# EnvFollower.net
KiCad netlist of a schematic drawn in EAGLE
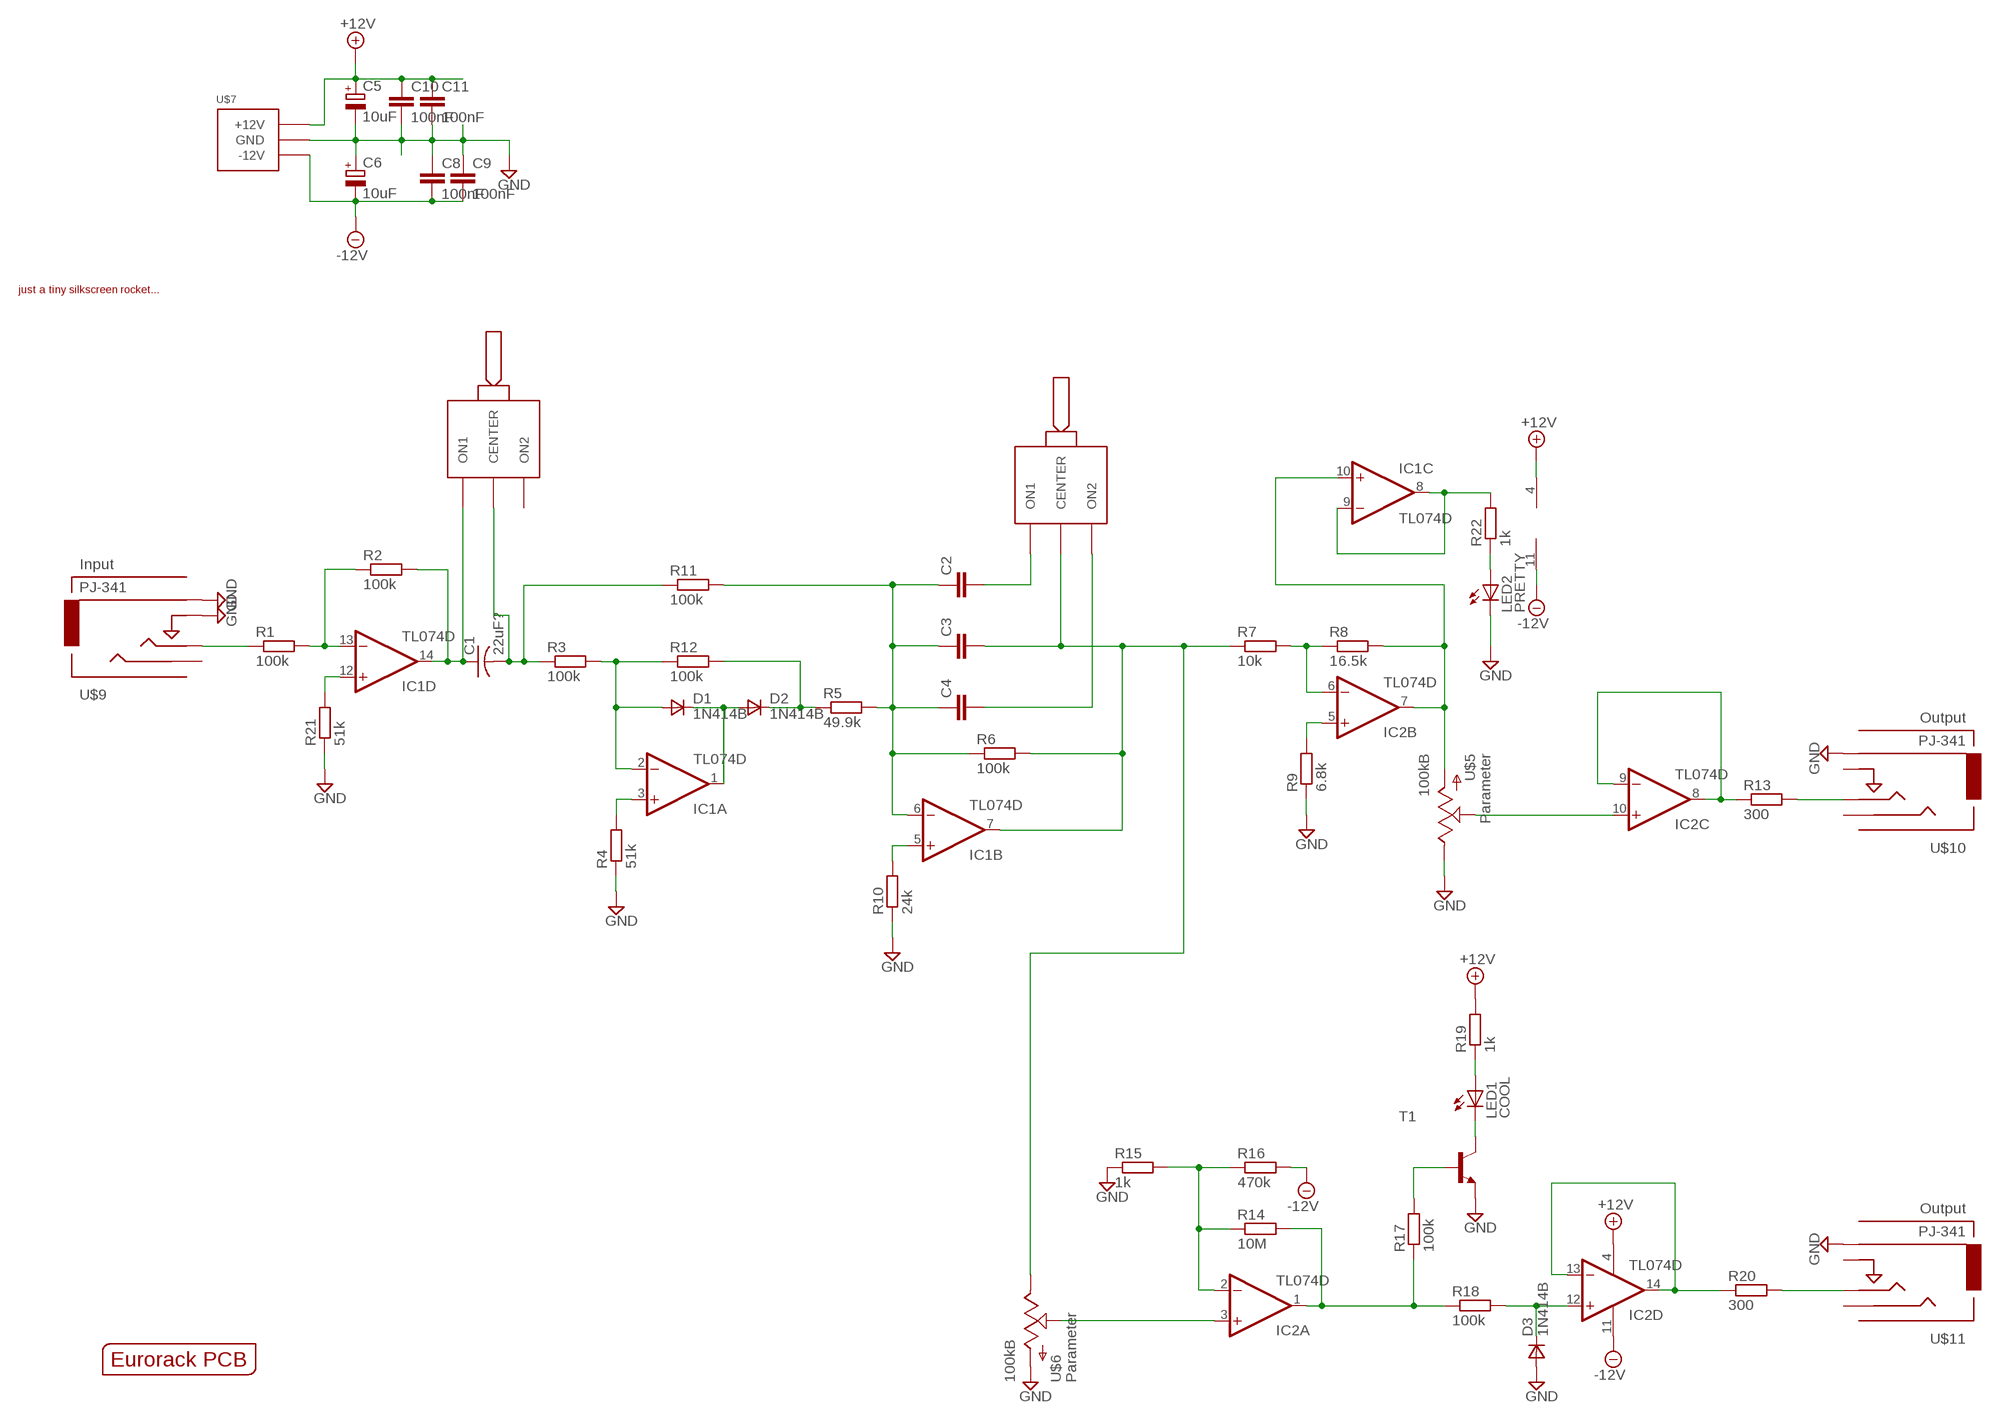
[diagram p0: schematic, sheet 1]

(export (version "E")
  (design (tool "Eeschema 10.0.6"))
  (components
    (comp (ref "C1")
      (value "22uF?")
      (footprint "eagle-import:C1210K")
      (libsource (lib "eagle-import") (part "C-USC1210K"))
    )
    (comp (ref "C2")
      (value "C-EUC0603K")
      (footprint "eagle-import:C0603K")
      (libsource (lib "eagle-import") (part "C-EUC0603K"))
    )
    (comp (ref "C3")
      (value "C-EUC0603K")
      (footprint "eagle-import:C0603K")
      (libsource (lib "eagle-import") (part "C-EUC0603K"))
    )
    (comp (ref "C4")
      (value "C-EUC0603K")
      (footprint "eagle-import:C0603K")
      (libsource (lib "eagle-import") (part "C-EUC0603K"))
    )
    (comp (ref "C5")
      (value "10uF")
      (footprint "eagle-import:153CLV-0505")
      (libsource (lib "eagle-import") (part "CPOL-EU153CLV-0505"))
    )
    (comp (ref "C6")
      (value "10uF")
      (footprint "eagle-import:153CLV-0505")
      (libsource (lib "eagle-import") (part "CPOL-EU153CLV-0505"))
    )
    (comp (ref "C8")
      (value "100nF")
      (footprint "eagle-import:C0603K")
      (libsource (lib "eagle-import") (part "C-EUC0603K"))
    )
    (comp (ref "C9")
      (value "100nF")
      (footprint "eagle-import:C0603K")
      (libsource (lib "eagle-import") (part "C-EUC0603K"))
    )
    (comp (ref "C10")
      (value "100nF")
      (footprint "eagle-import:C0603K")
      (libsource (lib "eagle-import") (part "C-EUC0603K"))
    )
    (comp (ref "C11")
      (value "100nF")
      (footprint "eagle-import:C0603K")
      (libsource (lib "eagle-import") (part "C-EUC0603K"))
    )
    (comp (ref "D1")
      (value "1N414B")
      (footprint "eagle-import:SOT-23")
      (fields (field (name "MPN") "CDSOT23-T03"))
      (libsource (lib "eagle-import") (part "DSOT23"))
    )
    (comp (ref "D2")
      (value "1N414B")
      (footprint "eagle-import:SOT-23")
      (fields (field (name "MPN") "CDSOT23-T03"))
      (libsource (lib "eagle-import") (part "DSOT23"))
    )
    (comp (ref "D3")
      (value "1N414B")
      (footprint "eagle-import:SOT-23")
      (fields (field (name "MPN") "CDSOT23-T03"))
      (libsource (lib "eagle-import") (part "DSOT23"))
    )
    (comp (ref "IC1")
      (value "TL074D")
      (footprint "eagle-import:SO14")
      (libsource (lib "eagle-import") (part "TL074D"))
    )
    (comp (ref "IC2")
      (value "TL074D")
      (footprint "eagle-import:SO14")
      (libsource (lib "eagle-import") (part "TL074D"))
    )
    (comp (ref "LED1")
      (value "COOL")
      (footprint "eagle-import:LED3MM")
      (libsource (lib "eagle-import") (part "LED3MM"))
    )
    (comp (ref "LED2")
      (value "PRETTY")
      (footprint "eagle-import:LED3MM")
      (libsource (lib "eagle-import") (part "LED3MM"))
    )
    (comp (ref "R1")
      (value "100k")
      (footprint "eagle-import:R0603")
      (libsource (lib "eagle-import") (part "R-EU_R0603"))
    )
    (comp (ref "R2")
      (value "100k")
      (footprint "eagle-import:R0603")
      (libsource (lib "eagle-import") (part "R-EU_R0603"))
    )
    (comp (ref "R3")
      (value "100k")
      (footprint "eagle-import:R0603")
      (libsource (lib "eagle-import") (part "R-EU_R0603"))
    )
    (comp (ref "R4")
      (value "51k")
      (footprint "eagle-import:R0603")
      (libsource (lib "eagle-import") (part "R-EU_R0603"))
    )
    (comp (ref "R5")
      (value "49.9k")
      (footprint "eagle-import:R0603")
      (libsource (lib "eagle-import") (part "R-EU_R0603"))
    )
    (comp (ref "R6")
      (value "100k")
      (footprint "eagle-import:R0603")
      (libsource (lib "eagle-import") (part "R-EU_R0603"))
    )
    (comp (ref "R7")
      (value "10k")
      (footprint "eagle-import:R0603")
      (libsource (lib "eagle-import") (part "R-EU_R0603"))
    )
    (comp (ref "R8")
      (value "16.5k")
      (footprint "eagle-import:R0603")
      (libsource (lib "eagle-import") (part "R-EU_R0603"))
    )
    (comp (ref "R9")
      (value "6.8k")
      (footprint "eagle-import:R0603")
      (libsource (lib "eagle-import") (part "R-EU_R0603"))
    )
    (comp (ref "R10")
      (value "24k")
      (footprint "eagle-import:R0603")
      (libsource (lib "eagle-import") (part "R-EU_R0603"))
    )
    (comp (ref "R11")
      (value "100k")
      (footprint "eagle-import:R0603")
      (libsource (lib "eagle-import") (part "R-EU_R0603"))
    )
    (comp (ref "R12")
      (value "100k")
      (footprint "eagle-import:R0603")
      (libsource (lib "eagle-import") (part "R-EU_R0603"))
    )
    (comp (ref "R13")
      (value "300")
      (footprint "eagle-import:R0603")
      (libsource (lib "eagle-import") (part "R-EU_R0603"))
    )
    (comp (ref "R14")
      (value "10M")
      (footprint "eagle-import:R0603")
      (libsource (lib "eagle-import") (part "R-EU_R0603"))
    )
    (comp (ref "R15")
      (value "1k")
      (footprint "eagle-import:R0603")
      (libsource (lib "eagle-import") (part "R-EU_R0603"))
    )
    (comp (ref "R16")
      (value "470k")
      (footprint "eagle-import:R0603")
      (libsource (lib "eagle-import") (part "R-EU_R0603"))
    )
    (comp (ref "R17")
      (value "100k")
      (footprint "eagle-import:R0603")
      (libsource (lib "eagle-import") (part "R-EU_R0603"))
    )
    (comp (ref "R18")
      (value "100k")
      (footprint "eagle-import:R0603")
      (libsource (lib "eagle-import") (part "R-EU_R0603"))
    )
    (comp (ref "R19")
      (value "1k")
      (footprint "eagle-import:R0603")
      (libsource (lib "eagle-import") (part "R-EU_R0603"))
    )
    (comp (ref "R20")
      (value "300")
      (footprint "eagle-import:R0603")
      (libsource (lib "eagle-import") (part "R-EU_R0603"))
    )
    (comp (ref "R21")
      (value "51k")
      (footprint "eagle-import:R0603")
      (libsource (lib "eagle-import") (part "R-EU_R0603"))
    )
    (comp (ref "R22")
      (value "1k")
      (footprint "eagle-import:R0603")
      (libsource (lib "eagle-import") (part "R-EU_R0603"))
    )
    (comp (ref "T1")
      (value "BCX70-NPN-SOT23-BEC")
      (footprint "eagle-import:SOT23-BEC")
      (libsource (lib "eagle-import") (part "-NPN-SOT23-BECBCX70"))
    )
    (comp (ref "U$1")
      (value "EURORACK_PCB4HP")
      (footprint "eagle-import:EURORACK4HPPCB")
      (libsource (lib "eagle-import") (part "EURORACK_PCB4HP"))
    )
    (comp (ref "U$2")
      (value "JUSTATINYROCKET")
      (footprint "eagle-import:JUSTATINYROCKET")
      (libsource (lib "eagle-import") (part "JUSTATINYROCKET"))
    )
    (comp (ref "U$4")
      (value "ONOFFON")
      (footprint "eagle-import:MULTICOMP1MS-ONOFFON")
      (libsource (lib "eagle-import") (part "ONOFFON"))
    )
    (comp (ref "U$5")
      (value "100kB")
      (footprint "eagle-import:OG-POTS_ALPS_POT_VERTICAL")
      (libsource (lib "eagle-import") (part "POTZEPHPOT"))
    )
    (comp (ref "U$6")
      (value "100kB")
      (footprint "eagle-import:OG-POTS_ALPS_POT_VERTICAL")
      (libsource (lib "eagle-import") (part "POTZEPHPOT"))
    )
    (comp (ref "U$7")
      (value "POWER_SIMPLE10-OTHERSIDE")
      (footprint "eagle-import:POWER_10_LABELSOTHERSIDE")
      (libsource (lib "eagle-import") (part "POWER_SIMPLE10-OTHERSIDE"))
    )
    (comp (ref "U$8")
      (value "ONOFFON")
      (footprint "eagle-import:MULTICOMP1MS-ONOFFON")
      (libsource (lib "eagle-import") (part "ONOFFON"))
    )
    (comp (ref "U$9")
      (value "PJ-341")
      (footprint "eagle-import:3.5MM-JACK-SWITCH-13MM-INPUT")
      (libsource (lib "eagle-import") (part "AUDIO-JACKINPUT"))
    )
    (comp (ref "U$10")
      (value "PJ-341")
      (footprint "eagle-import:3.5MM-JACK-SWITCH-13MM-OUTPUT")
      (libsource (lib "eagle-import") (part "AUDIO-JACKOUTPUT"))
    )
    (comp (ref "U$11")
      (value "PJ-341")
      (footprint "eagle-import:3.5MM-JACK-SWITCH-13MM-OUTPUT")
      (libsource (lib "eagle-import") (part "AUDIO-JACKOUTPUT"))
    )
  )
  (nets
    (net (code "1") (name "+12V") (class "Default")
      (node (ref "C10") (pin "1") (pinfunction "1_1") (pintype "passive"))
      (node (ref "C11") (pin "1") (pinfunction "1_1") (pintype "passive"))
      (node (ref "C5") (pin "+") (pinfunction "+_+") (pintype "passive"))
      (node (ref "IC1") (pin "4") (pinfunction "V+_4") (pintype "power_in"))
      (node (ref "IC2") (pin "4") (pinfunction "V+_4") (pintype "power_in"))
      (node (ref "R19") (pin "2") (pinfunction "2_2") (pintype "passive"))
      (node (ref "U$7") (pin "10") (pinfunction "+12V_10") (pintype "bidirectional"))
      (node (ref "U$7") (pin "9") (pinfunction "+12V_9") (pintype "bidirectional"))
    )
    (net (code "2") (name "-12V") (class "Default")
      (node (ref "C6") (pin "-") (pinfunction "-_-") (pintype "passive"))
      (node (ref "C8") (pin "2") (pinfunction "2_2") (pintype "passive"))
      (node (ref "C9") (pin "2") (pinfunction "2_2") (pintype "passive"))
      (node (ref "IC1") (pin "11") (pinfunction "V-_11") (pintype "power_in"))
      (node (ref "IC2") (pin "11") (pinfunction "V-_11") (pintype "power_in"))
      (node (ref "R16") (pin "2") (pinfunction "2_2") (pintype "passive"))
      (node (ref "U$7") (pin "1") (pinfunction "-12V_1") (pintype "bidirectional"))
      (node (ref "U$7") (pin "2") (pinfunction "-12V_2") (pintype "bidirectional"))
    )
    (net (code "3") (name "GND") (class "Default")
      (node (ref "C10") (pin "2") (pinfunction "2_2") (pintype "passive"))
      (node (ref "C11") (pin "2") (pinfunction "2_2") (pintype "passive"))
      (node (ref "C5") (pin "-") (pinfunction "-_-") (pintype "passive"))
      (node (ref "C6") (pin "+") (pinfunction "+_+") (pintype "passive"))
      (node (ref "C8") (pin "1") (pinfunction "1_1") (pintype "passive"))
      (node (ref "C9") (pin "1") (pinfunction "1_1") (pintype "passive"))
      (node (ref "D3") (pin "3") (pinfunction "A_3") (pintype "passive"))
      (node (ref "LED2") (pin "K") (pinfunction "C_K") (pintype "passive"))
      (node (ref "R10") (pin "1") (pinfunction "1_1") (pintype "passive"))
      (node (ref "R15") (pin "1") (pinfunction "1_1") (pintype "passive"))
      (node (ref "R21") (pin "1") (pinfunction "1_1") (pintype "passive"))
      (node (ref "R4") (pin "1") (pinfunction "1_1") (pintype "passive"))
      (node (ref "R9") (pin "1") (pinfunction "1_1") (pintype "passive"))
      (node (ref "T1") (pin "E") (pinfunction "E_E") (pintype "passive"))
      (node (ref "U$10") (pin "RING@3") (pinfunction "RING_RING@3") (pintype "bidirectional"))
      (node (ref "U$11") (pin "RING@3") (pinfunction "RING_RING@3") (pintype "bidirectional"))
      (node (ref "U$5") (pin "P$1") (pinfunction "E_P$1") (pintype "passive"))
      (node (ref "U$6") (pin "P$3") (pinfunction "A_P$3") (pintype "passive"))
      (node (ref "U$7") (pin "3") (pinfunction "GND_3") (pintype "bidirectional"))
      (node (ref "U$7") (pin "4") (pinfunction "GND_4") (pintype "bidirectional"))
      (node (ref "U$7") (pin "5") (pinfunction "GND_5") (pintype "bidirectional"))
      (node (ref "U$7") (pin "6") (pinfunction "GND_6") (pintype "bidirectional"))
      (node (ref "U$7") (pin "7") (pinfunction "GND_7") (pintype "bidirectional"))
      (node (ref "U$7") (pin "8") (pinfunction "GND_8") (pintype "bidirectional"))
      (node (ref "U$9") (pin "RING@3") (pinfunction "RING_RING@3") (pintype "bidirectional"))
      (node (ref "U$9") (pin "SWITCH@3") (pinfunction "SWITCH_SWITCH@3") (pintype "bidirectional"))
    )
    (net (code "4") (name "Net-(D1-A)") (class "Default")
      (node (ref "D1") (pin "3") (pinfunction "A_3") (pintype "passive"))
      (node (ref "IC1") (pin "2") (pinfunction "-IN_2") (pintype "input"))
      (node (ref "R12") (pin "1") (pinfunction "1_1") (pintype "passive"))
      (node (ref "R3") (pin "2") (pinfunction "2_2") (pintype "passive"))
    )
    (net (code "5") (name "Net-(D1-C)") (class "Default")
      (node (ref "D1") (pin "1") (pinfunction "C_1") (pintype "passive"))
      (node (ref "D2") (pin "3") (pinfunction "A_3") (pintype "passive"))
      (node (ref "IC1") (pin "1") (pinfunction "OUT_1") (pintype "output"))
    )
    (net (code "6") (name "Net-(D2-C)") (class "Default")
      (node (ref "D2") (pin "1") (pinfunction "C_1") (pintype "passive"))
      (node (ref "R12") (pin "2") (pinfunction "2_2") (pintype "passive"))
      (node (ref "R5") (pin "1") (pinfunction "1_1") (pintype "passive"))
    )
    (net (code "7") (name "Net-(D3-C)") (class "Default")
      (node (ref "D3") (pin "1") (pinfunction "C_1") (pintype "passive"))
      (node (ref "IC2") (pin "12") (pinfunction "+IN_12") (pintype "input"))
      (node (ref "R18") (pin "2") (pinfunction "2_2") (pintype "passive"))
    )
    (net (code "8") (name "Net-(IC1A-+IN)") (class "Default")
      (node (ref "IC1") (pin "3") (pinfunction "+IN_3") (pintype "input"))
      (node (ref "R4") (pin "2") (pinfunction "2_2") (pintype "passive"))
    )
    (net (code "9") (name "Net-(IC1B-+IN)") (class "Default")
      (node (ref "IC1") (pin "5") (pinfunction "+IN_5") (pintype "input"))
      (node (ref "R10") (pin "2") (pinfunction "2_2") (pintype "passive"))
    )
    (net (code "10") (name "Net-(IC1B--IN)") (class "Default")
      (node (ref "C2") (pin "1") (pinfunction "1_1") (pintype "passive"))
      (node (ref "C3") (pin "1") (pinfunction "1_1") (pintype "passive"))
      (node (ref "C4") (pin "1") (pinfunction "1_1") (pintype "passive"))
      (node (ref "IC1") (pin "6") (pinfunction "-IN_6") (pintype "input"))
      (node (ref "R11") (pin "2") (pinfunction "2_2") (pintype "passive"))
      (node (ref "R5") (pin "2") (pinfunction "2_2") (pintype "passive"))
      (node (ref "R6") (pin "1") (pinfunction "1_1") (pintype "passive"))
    )
    (net (code "11") (name "Net-(IC1B-OUT)") (class "Default")
      (node (ref "C3") (pin "2") (pinfunction "2_2") (pintype "passive"))
      (node (ref "IC1") (pin "7") (pinfunction "OUT_7") (pintype "output"))
      (node (ref "R6") (pin "2") (pinfunction "2_2") (pintype "passive"))
      (node (ref "R7") (pin "1") (pinfunction "1_1") (pintype "passive"))
      (node (ref "U$6") (pin "P$1") (pinfunction "E_P$1") (pintype "passive"))
      (node (ref "U$8") (pin "2") (pinfunction "CENTER_2") (pintype "bidirectional"))
    )
    (net (code "12") (name "Net-(IC1C-+IN)") (class "Default")
      (node (ref "IC1") (pin "10") (pinfunction "+IN_10") (pintype "input"))
      (node (ref "IC2") (pin "7") (pinfunction "OUT_7") (pintype "output"))
      (node (ref "R8") (pin "2") (pinfunction "2_2") (pintype "passive"))
      (node (ref "U$5") (pin "P$3") (pinfunction "A_P$3") (pintype "passive"))
    )
    (net (code "13") (name "Net-(IC1C--IN)") (class "Default")
      (node (ref "IC1") (pin "8") (pinfunction "OUT_8") (pintype "output"))
      (node (ref "IC1") (pin "9") (pinfunction "-IN_9") (pintype "input"))
      (node (ref "R22") (pin "2") (pinfunction "2_2") (pintype "passive"))
    )
    (net (code "14") (name "Net-(IC1D-+IN)") (class "Default")
      (node (ref "IC1") (pin "12") (pinfunction "+IN_12") (pintype "input"))
      (node (ref "R21") (pin "2") (pinfunction "2_2") (pintype "passive"))
    )
    (net (code "15") (name "Net-(IC1D--IN)") (class "Default")
      (node (ref "IC1") (pin "13") (pinfunction "-IN_13") (pintype "input"))
      (node (ref "R1") (pin "2") (pinfunction "2_2") (pintype "passive"))
      (node (ref "R2") (pin "1") (pinfunction "1_1") (pintype "passive"))
    )
    (net (code "16") (name "Net-(IC1D-OUT)") (class "Default")
      (node (ref "C1") (pin "1") (pinfunction "1_1") (pintype "passive"))
      (node (ref "IC1") (pin "14") (pinfunction "OUT_14") (pintype "output"))
      (node (ref "R2") (pin "2") (pinfunction "2_2") (pintype "passive"))
      (node (ref "U$4") (pin "1") (pinfunction "ON1_1") (pintype "bidirectional"))
    )
    (net (code "17") (name "Net-(IC2A-+IN)") (class "Default")
      (node (ref "IC2") (pin "3") (pinfunction "+IN_3") (pintype "input"))
      (node (ref "U$6") (pin "P$2") (pinfunction "S_P$2") (pintype "passive"))
    )
    (net (code "18") (name "Net-(IC2A--IN)") (class "Default")
      (node (ref "IC2") (pin "2") (pinfunction "-IN_2") (pintype "input"))
      (node (ref "R14") (pin "1") (pinfunction "1_1") (pintype "passive"))
      (node (ref "R15") (pin "2") (pinfunction "2_2") (pintype "passive"))
      (node (ref "R16") (pin "1") (pinfunction "1_1") (pintype "passive"))
    )
    (net (code "19") (name "Net-(IC2A-OUT)") (class "Default")
      (node (ref "IC2") (pin "1") (pinfunction "OUT_1") (pintype "output"))
      (node (ref "R14") (pin "2") (pinfunction "2_2") (pintype "passive"))
      (node (ref "R17") (pin "1") (pinfunction "1_1") (pintype "passive"))
      (node (ref "R18") (pin "1") (pinfunction "1_1") (pintype "passive"))
    )
    (net (code "20") (name "Net-(IC2B-+IN)") (class "Default")
      (node (ref "IC2") (pin "5") (pinfunction "+IN_5") (pintype "input"))
      (node (ref "R9") (pin "2") (pinfunction "2_2") (pintype "passive"))
    )
    (net (code "21") (name "Net-(IC2B--IN)") (class "Default")
      (node (ref "IC2") (pin "6") (pinfunction "-IN_6") (pintype "input"))
      (node (ref "R7") (pin "2") (pinfunction "2_2") (pintype "passive"))
      (node (ref "R8") (pin "1") (pinfunction "1_1") (pintype "passive"))
    )
    (net (code "22") (name "Net-(IC2C-+IN)") (class "Default")
      (node (ref "IC2") (pin "10") (pinfunction "+IN_10") (pintype "input"))
      (node (ref "U$5") (pin "P$2") (pinfunction "S_P$2") (pintype "passive"))
    )
    (net (code "23") (name "Net-(IC2C--IN)") (class "Default")
      (node (ref "IC2") (pin "8") (pinfunction "OUT_8") (pintype "output"))
      (node (ref "IC2") (pin "9") (pinfunction "-IN_9") (pintype "input"))
      (node (ref "R13") (pin "1") (pinfunction "1_1") (pintype "passive"))
    )
    (net (code "24") (name "Net-(IC2D--IN)") (class "Default")
      (node (ref "IC2") (pin "13") (pinfunction "-IN_13") (pintype "input"))
      (node (ref "IC2") (pin "14") (pinfunction "OUT_14") (pintype "output"))
      (node (ref "R20") (pin "1") (pinfunction "1_1") (pintype "passive"))
    )
    (net (code "25") (name "Net-(LED1-C)") (class "Default")
      (node (ref "LED1") (pin "K") (pinfunction "C_K") (pintype "passive"))
      (node (ref "T1") (pin "C") (pinfunction "C_C") (pintype "passive"))
    )
    (net (code "26") (name "Net-(LED1-PadA)") (class "Default")
      (node (ref "LED1") (pin "A") (pinfunction "A_A") (pintype "passive"))
      (node (ref "R19") (pin "1") (pinfunction "1_1") (pintype "passive"))
    )
    (net (code "27") (name "Net-(LED2-PadA)") (class "Default")
      (node (ref "LED2") (pin "A") (pinfunction "A_A") (pintype "passive"))
      (node (ref "R22") (pin "1") (pinfunction "1_1") (pintype "passive"))
    )
    (net (code "28") (name "Net-(R17-Pad2)") (class "Default")
      (node (ref "R17") (pin "2") (pinfunction "2_2") (pintype "passive"))
      (node (ref "T1") (pin "B") (pinfunction "B_B") (pintype "passive"))
    )
    (net (code "29") (name "Net-(U$4-CENTER)") (class "Default")
      (node (ref "C1") (pin "2") (pinfunction "2_2") (pintype "passive"))
      (node (ref "R11") (pin "1") (pinfunction "1_1") (pintype "passive"))
      (node (ref "R3") (pin "1") (pinfunction "1_1") (pintype "passive"))
      (node (ref "U$4") (pin "2") (pinfunction "CENTER_2") (pintype "bidirectional"))
    )
    (net (code "30") (name "Net-(U$8-ON1)") (class "Default")
      (node (ref "C2") (pin "2") (pinfunction "2_2") (pintype "passive"))
      (node (ref "U$8") (pin "1") (pinfunction "ON1_1") (pintype "bidirectional"))
    )
    (net (code "31") (name "Net-(U$8-ON2)") (class "Default")
      (node (ref "C4") (pin "2") (pinfunction "2_2") (pintype "passive"))
      (node (ref "U$8") (pin "3") (pinfunction "ON2_3") (pintype "bidirectional"))
    )
    (net (code "32") (name "Net-(U$9-TIP)") (class "Default")
      (node (ref "R1") (pin "1") (pinfunction "1_1") (pintype "passive"))
      (node (ref "U$9") (pin "TIP@3") (pinfunction "TIP_TIP@3") (pintype "bidirectional"))
    )
    (net (code "33") (name "Net-(U$10-TIP)") (class "Default")
      (node (ref "R13") (pin "2") (pinfunction "2_2") (pintype "passive"))
      (node (ref "U$10") (pin "TIP@3") (pinfunction "TIP_TIP@3") (pintype "bidirectional"))
    )
    (net (code "34") (name "Net-(U$11-TIP)") (class "Default")
      (node (ref "R20") (pin "2") (pinfunction "2_2") (pintype "passive"))
      (node (ref "U$11") (pin "TIP@3") (pinfunction "TIP_TIP@3") (pintype "bidirectional"))
    )
    (net (code "35") (name "unconnected-(U$4-ON2-Pad3)") (class "Default")
      (node (ref "U$4") (pin "3") (pinfunction "ON2_3") (pintype "bidirectional"))
    )
    (net (code "36") (name "unconnected-(U$9-SECOND-PadSECOND@3)") (class "Default")
      (node (ref "U$9") (pin "SECOND@3") (pinfunction "SECOND_SECOND@3") (pintype "bidirectional"))
    )
    (net (code "37") (name "unconnected-(U$10-SECOND-PadSECOND@3)") (class "Default")
      (node (ref "U$10") (pin "SECOND@3") (pinfunction "SECOND_SECOND@3") (pintype "bidirectional"))
    )
    (net (code "38") (name "unconnected-(U$10-SWITCH-PadSWITCH@3)") (class "Default")
      (node (ref "U$10") (pin "SWITCH@3") (pinfunction "SWITCH_SWITCH@3") (pintype "bidirectional"))
    )
    (net (code "39") (name "unconnected-(U$11-SECOND-PadSECOND@3)") (class "Default")
      (node (ref "U$11") (pin "SECOND@3") (pinfunction "SECOND_SECOND@3") (pintype "bidirectional"))
    )
    (net (code "40") (name "unconnected-(U$11-SWITCH-PadSWITCH@3)") (class "Default")
      (node (ref "U$11") (pin "SWITCH@3") (pinfunction "SWITCH_SWITCH@3") (pintype "bidirectional"))
    )
  )
)
